# 02A-007.net
KiCad netlist of a schematic drawn in EAGLE
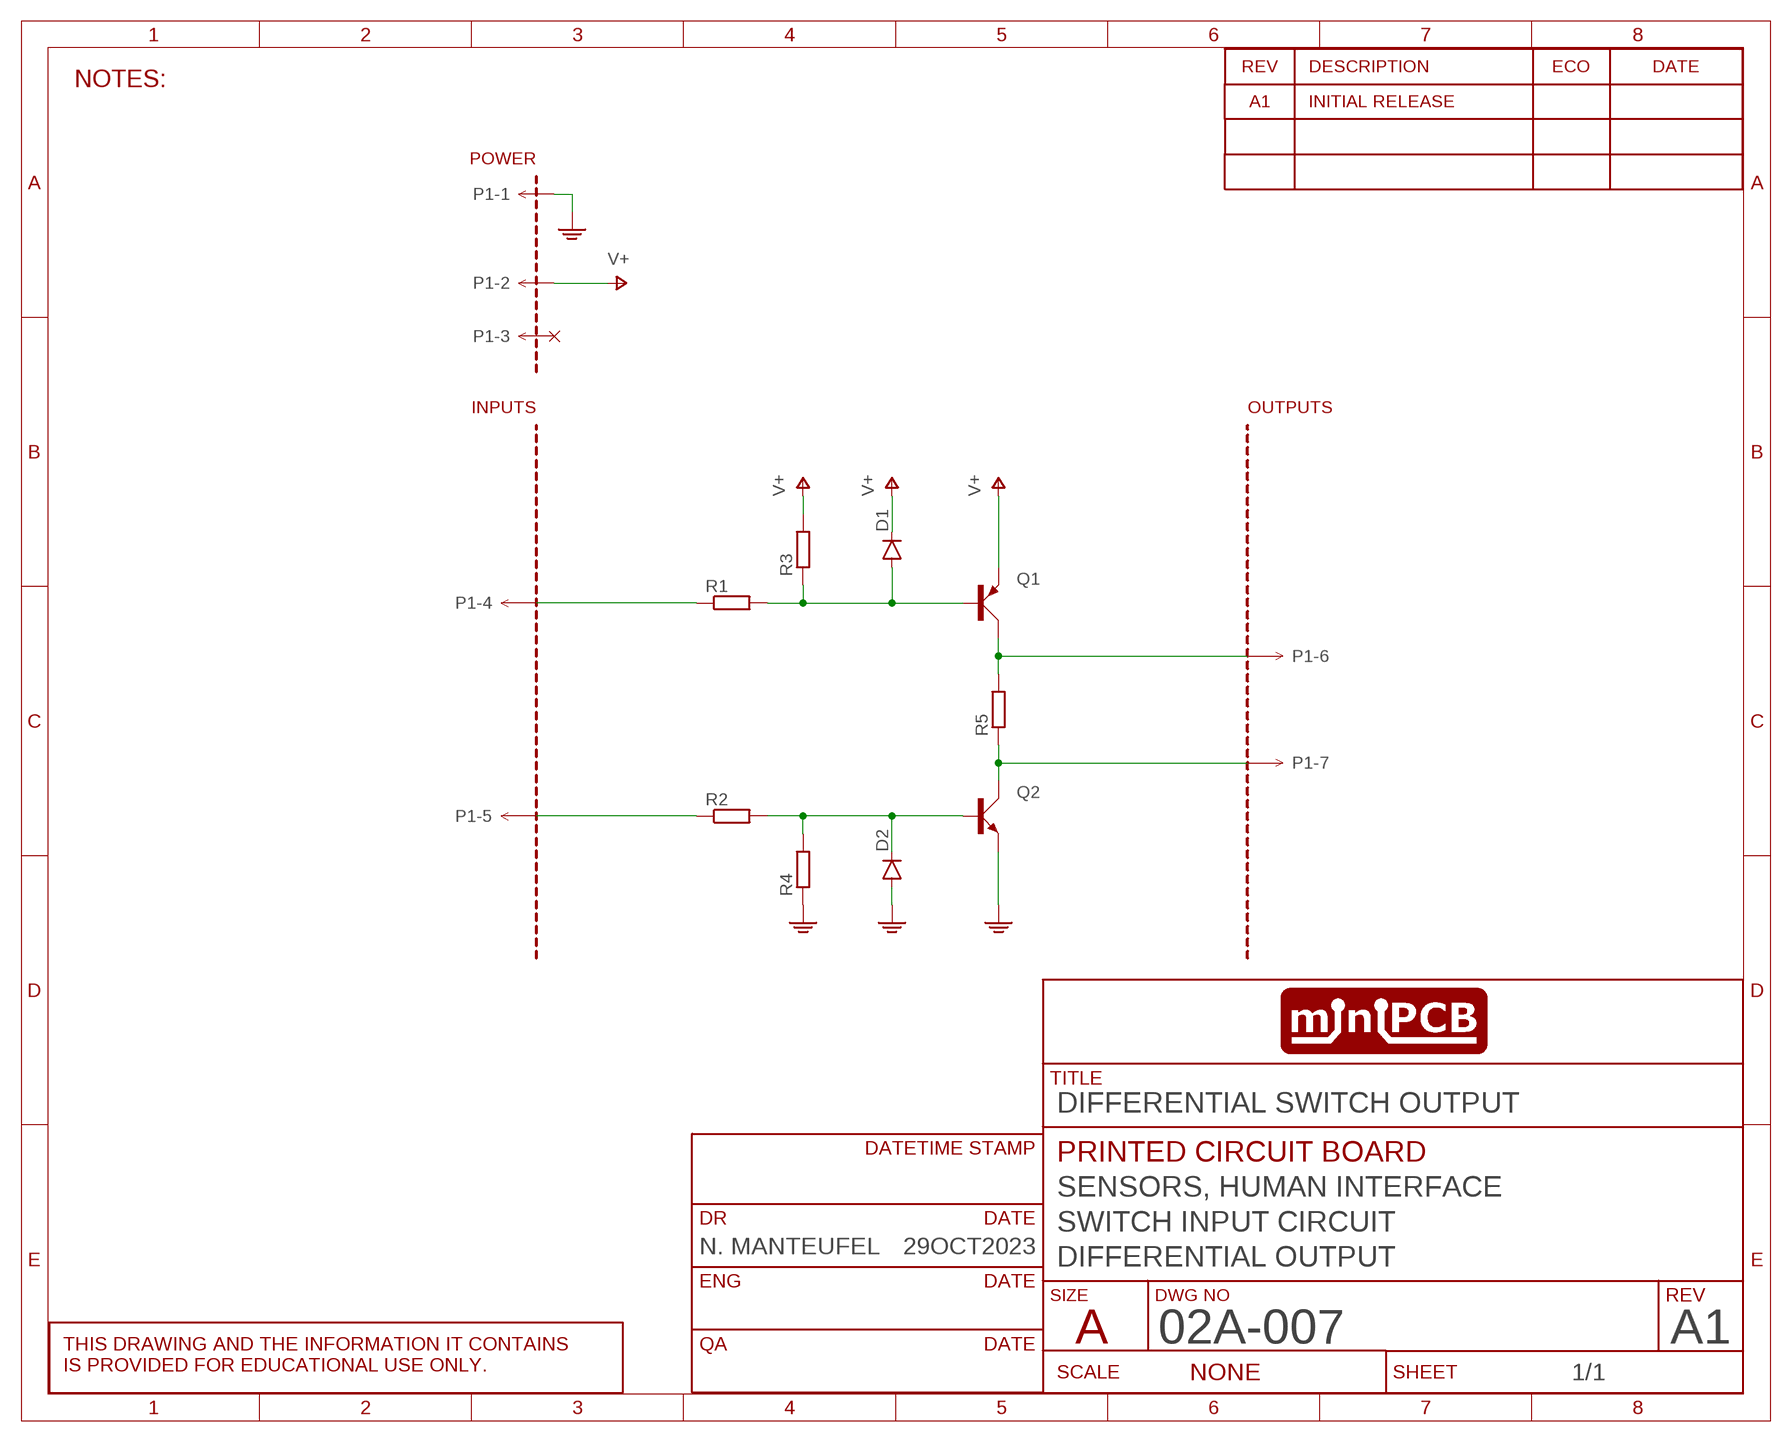
[diagram p0: schematic, sheet 1]

(export (version "E")
  (design (tool "Eeschema 10.0.6"))
  (components
    (comp (ref "D1")
      (value "DIODESMD")
      (footprint "eagle-import:DO214AC")
      (libsource (lib "eagle-import") (part "DIODESMD"))
    )
    (comp (ref "D2")
      (value "DIODESMD")
      (footprint "eagle-import:DO214AC")
      (libsource (lib "eagle-import") (part "DIODESMD"))
    )
    (comp (ref "P1")
      (value "MINIPCB_7P")
      (footprint "eagle-import:PINS_1X7")
      (libsource (lib "eagle-import") (part "MINIPCB_7P"))
    )
    (comp (ref "PCB1")
      (value "MINIPCB_0P00A-20X25")
      (footprint "eagle-import:MINIPCB_00A_20X25")
      (fields (field (name "PART_NUMBER") "02A-007") (field (name "REVISION") "A1-01"))
      (libsource (lib "eagle-import") (part "MINIPCB_0P00A-20X25"))
    )
    (comp (ref "Q1")
      (value "BJT_PNPBEC")
      (footprint "eagle-import:SOT23")
      (libsource (lib "eagle-import") (part "BJT_PNPBEC"))
    )
    (comp (ref "Q2")
      (value "BJT_NPNBEC")
      (footprint "eagle-import:SOT23")
      (libsource (lib "eagle-import") (part "BJT_NPNBEC"))
    )
    (comp (ref "R1")
      (value "RESISTORSMD")
      (footprint "eagle-import:R0805")
      (libsource (lib "eagle-import") (part "RESISTORSMD"))
    )
    (comp (ref "R2")
      (value "RESISTORSMD")
      (footprint "eagle-import:R0805")
      (libsource (lib "eagle-import") (part "RESISTORSMD"))
    )
    (comp (ref "R3")
      (value "RESISTORSMD")
      (footprint "eagle-import:R0805")
      (libsource (lib "eagle-import") (part "RESISTORSMD"))
    )
    (comp (ref "R4")
      (value "RESISTORSMD")
      (footprint "eagle-import:R0805")
      (libsource (lib "eagle-import") (part "RESISTORSMD"))
    )
    (comp (ref "R5")
      (value "RESISTORSMD")
      (footprint "eagle-import:R0805")
      (libsource (lib "eagle-import") (part "RESISTORSMD"))
    )
  )
  (nets
    (net (code "1") (name "GND") (class "Default")
      (node (ref "D2") (pin "A") (pinfunction "A_A") (pintype "passive"))
      (node (ref "P1") (pin "1") (pinfunction "1_1") (pintype "bidirectional"))
      (node (ref "Q2") (pin "2") (pinfunction "E_2") (pintype "passive"))
      (node (ref "R4") (pin "1") (pinfunction "1_1") (pintype "passive"))
    )
    (net (code "2") (name "Net-(P1D-1)") (class "Default")
      (node (ref "P1") (pin "4") (pinfunction "1_4") (pintype "bidirectional"))
      (node (ref "R1") (pin "1") (pinfunction "1_1") (pintype "passive"))
    )
    (net (code "3") (name "Net-(P1E-1)") (class "Default")
      (node (ref "P1") (pin "5") (pinfunction "1_5") (pintype "bidirectional"))
      (node (ref "R2") (pin "1") (pinfunction "1_1") (pintype "passive"))
    )
    (net (code "4") (name "Net-(P1F-1)") (class "Default")
      (node (ref "P1") (pin "6") (pinfunction "1_6") (pintype "bidirectional"))
      (node (ref "Q1") (pin "3") (pinfunction "C_3") (pintype "passive"))
      (node (ref "R5") (pin "2") (pinfunction "2_2") (pintype "passive"))
    )
    (net (code "5") (name "Net-(P1G-1)") (class "Default")
      (node (ref "P1") (pin "7") (pinfunction "1_7") (pintype "bidirectional"))
      (node (ref "Q2") (pin "3") (pinfunction "C_3") (pintype "passive"))
      (node (ref "R5") (pin "1") (pinfunction "1_1") (pintype "passive"))
    )
    (net (code "6") (name "Net-(Q1-B)") (class "Default")
      (node (ref "D1") (pin "A") (pinfunction "A_A") (pintype "passive"))
      (node (ref "Q1") (pin "1") (pinfunction "B_1") (pintype "passive"))
      (node (ref "R1") (pin "2") (pinfunction "2_2") (pintype "passive"))
      (node (ref "R3") (pin "1") (pinfunction "1_1") (pintype "passive"))
    )
    (net (code "7") (name "Net-(Q2-B)") (class "Default")
      (node (ref "D2") (pin "C") (pinfunction "C_C") (pintype "passive"))
      (node (ref "Q2") (pin "1") (pinfunction "B_1") (pintype "passive"))
      (node (ref "R2") (pin "2") (pinfunction "2_2") (pintype "passive"))
      (node (ref "R4") (pin "2") (pinfunction "2_2") (pintype "passive"))
    )
    (net (code "8") (name "V+") (class "Default")
      (node (ref "D1") (pin "C") (pinfunction "C_C") (pintype "passive"))
      (node (ref "P1") (pin "2") (pinfunction "1_2") (pintype "bidirectional"))
      (node (ref "Q1") (pin "2") (pinfunction "E_2") (pintype "passive"))
      (node (ref "R3") (pin "2") (pinfunction "2_2") (pintype "passive"))
    )
    (net (code "9") (name "unconnected-(P1C-1-Pad3)") (class "Default")
      (node (ref "P1") (pin "3") (pinfunction "1_3") (pintype "bidirectional"))
    )
  )
)
